# design.net
KiCad netlist of a schematic drawn in EasyEDA Pro
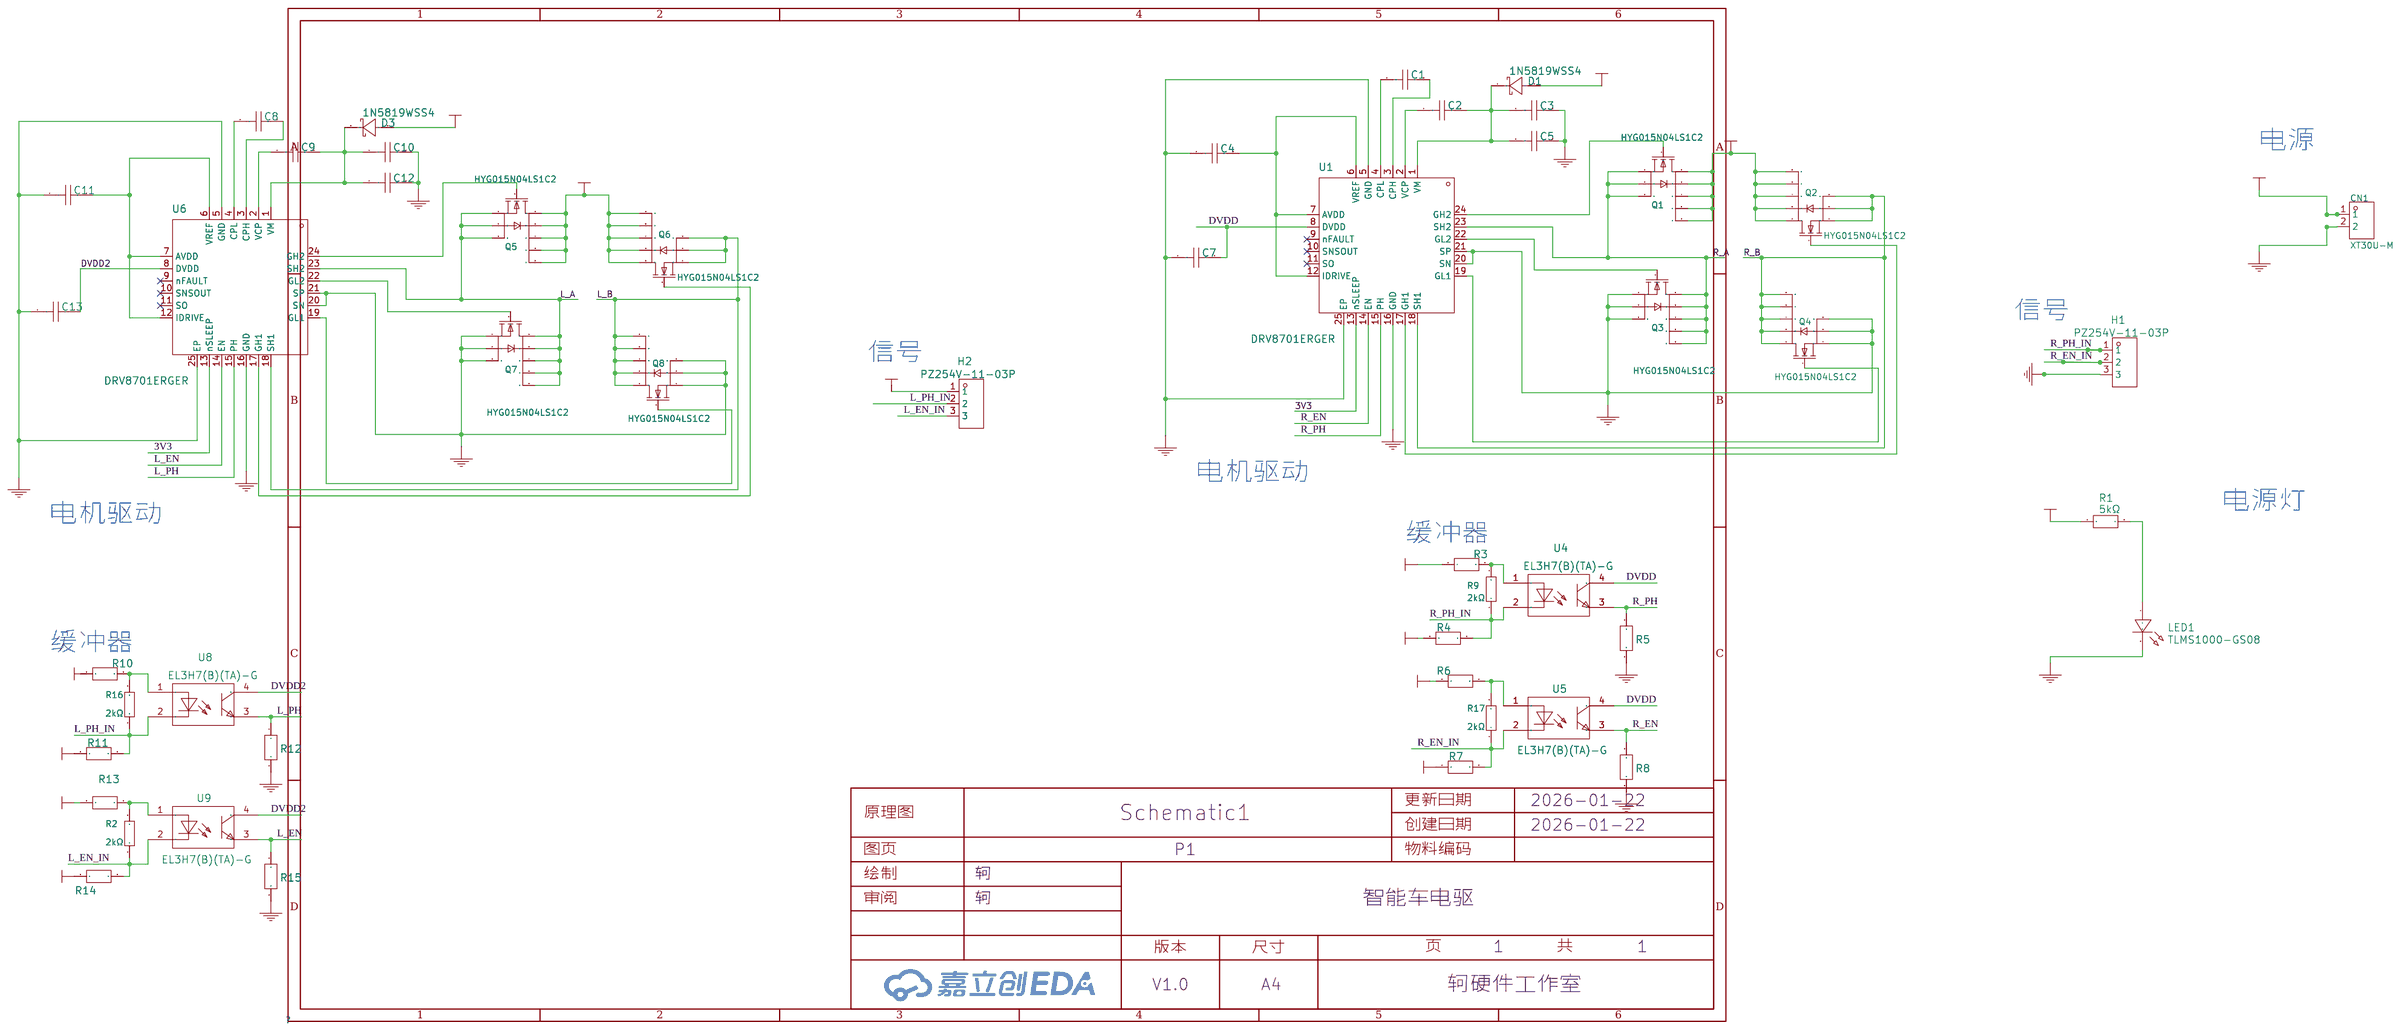
[diagram p0: schematic sheet]

(export (version "E")
  (design (tool "Eeschema 10.0.6"))
  (components
    (comp (ref "C1")
      (value "100nF")
      (fields (field (name "Manufacturer Part") "CC0805KRX7R9BB104"))
      (libsource (lib "easyedapro") (part "100nF"))
    )
    (comp (ref "C2")
      (value "1uF")
      (fields (field (name "Manufacturer Part") "CC0805KKX7R9BB105"))
      (libsource (lib "easyedapro") (part "1uF"))
    )
    (comp (ref "C3")
      (value "10nF")
      (fields (field (name "Manufacturer Part") "CC0805KRX7R9BB103"))
      (libsource (lib "easyedapro") (part "10uF"))
    )
    (comp (ref "C4")
      (value "1uF")
      (fields (field (name "Manufacturer Part") "CC0805KKX7R9BB105"))
      (libsource (lib "easyedapro") (part "1uF"))
    )
    (comp (ref "C5")
      (value "100nF")
      (fields (field (name "Manufacturer Part") "CC0805KRX7R9BB104"))
      (libsource (lib "easyedapro") (part "100nF"))
    )
    (comp (ref "C7")
      (value "1uF")
      (fields (field (name "Manufacturer Part") "CC0805KKX7R9BB105"))
      (libsource (lib "easyedapro") (part "1uF"))
    )
    (comp (ref "C8")
      (value "100nF")
      (fields (field (name "Manufacturer Part") "CC0805KRX7R9BB104"))
      (libsource (lib "easyedapro") (part "100nF"))
    )
    (comp (ref "C9")
      (value "1uF")
      (fields (field (name "Manufacturer Part") "CC0805KKX7R9BB105"))
      (libsource (lib "easyedapro") (part "1uF"))
    )
    (comp (ref "C10")
      (value "10nF")
      (fields (field (name "Manufacturer Part") "CC0805KRX7R9BB103"))
      (libsource (lib "easyedapro") (part "10uF"))
    )
    (comp (ref "C11")
      (value "1uF")
      (fields (field (name "Manufacturer Part") "CC0805KKX7R9BB105"))
      (libsource (lib "easyedapro") (part "1uF"))
    )
    (comp (ref "C12")
      (value "100nF")
      (fields (field (name "Manufacturer Part") "CC0805KRX7R9BB104"))
      (libsource (lib "easyedapro") (part "100nF"))
    )
    (comp (ref "C13")
      (value "1uF")
      (fields (field (name "Manufacturer Part") "CC0805KKX7R9BB105"))
      (libsource (lib "easyedapro") (part "1uF"))
    )
    (comp (ref "CN1")
      (value "XT30U-M")
      (fields (field (name "Manufacturer") "AMASS(艾迈斯)"))
      (libsource (lib "easyedapro") (part "XT30U-M"))
    )
    (comp (ref "D1")
      (value "1N5819WSS4")
      (fields (field (name "Manufacturer") "JSMSEMI(杰盛微)"))
      (libsource (lib "easyedapro") (part "1N5819WS S4"))
    )
    (comp (ref "D3")
      (value "1N5819WSS4")
      (fields (field (name "Manufacturer") "JSMSEMI(杰盛微)"))
      (libsource (lib "easyedapro") (part "1N5819WS S4"))
    )
    (comp (ref "H1")
      (value "PZ254V-11-03P")
      (fields (field (name "Manufacturer") "XFCN(兴飞)"))
      (libsource (lib "easyedapro") (part "PZ254V-11-03P_C2937625"))
    )
    (comp (ref "H2")
      (value "PZ254V-11-03P")
      (fields (field (name "Manufacturer") "XFCN(兴飞)"))
      (libsource (lib "easyedapro") (part "PZ254V-11-03P_C2937625"))
    )
    (comp (ref "LED1")
      (value "TLMS1000-GS08")
      (fields (field (name "Manufacturer") "VISHAY(威世)"))
      (libsource (lib "easyedapro") (part "LED-0603_G"))
    )
    (comp (ref "Q1")
      (value "HYG015N04LS1C2")
      (footprint "easyedapro:DFN-8_L5.9-W5.2-P1.27-LS6.2-BL")
      (fields (field (name "Manufacturer") "HUAYI(华羿微)"))
      (libsource (lib "easyedapro") (part "HYG015N04LS1C2"))
    )
    (comp (ref "Q2")
      (value "HYG015N04LS1C2")
      (footprint "easyedapro:DFN-8_L5.9-W5.2-P1.27-LS6.2-BL")
      (fields (field (name "Manufacturer") "HUAYI(华羿微)"))
      (libsource (lib "easyedapro") (part "HYG015N04LS1C2"))
    )
    (comp (ref "Q3")
      (value "HYG015N04LS1C2")
      (footprint "easyedapro:DFN-8_L5.9-W5.2-P1.27-LS6.2-BL")
      (fields (field (name "Manufacturer") "HUAYI(华羿微)"))
      (libsource (lib "easyedapro") (part "HYG015N04LS1C2"))
    )
    (comp (ref "Q4")
      (value "HYG015N04LS1C2")
      (footprint "easyedapro:DFN-8_L5.9-W5.2-P1.27-LS6.2-BL")
      (fields (field (name "Manufacturer") "HUAYI(华羿微)"))
      (libsource (lib "easyedapro") (part "HYG015N04LS1C2"))
    )
    (comp (ref "Q5")
      (value "HYG015N04LS1C2")
      (footprint "easyedapro:DFN-8_L5.9-W5.2-P1.27-LS6.2-BL")
      (fields (field (name "Manufacturer") "HUAYI(华羿微)"))
      (libsource (lib "easyedapro") (part "HYG015N04LS1C2"))
    )
    (comp (ref "Q6")
      (value "HYG015N04LS1C2")
      (footprint "easyedapro:DFN-8_L5.9-W5.2-P1.27-LS6.2-BL")
      (fields (field (name "Manufacturer") "HUAYI(华羿微)"))
      (libsource (lib "easyedapro") (part "HYG015N04LS1C2"))
    )
    (comp (ref "Q7")
      (value "HYG015N04LS1C2")
      (footprint "easyedapro:DFN-8_L5.9-W5.2-P1.27-LS6.2-BL")
      (fields (field (name "Manufacturer") "HUAYI(华羿微)"))
      (libsource (lib "easyedapro") (part "HYG015N04LS1C2"))
    )
    (comp (ref "Q8")
      (value "HYG015N04LS1C2")
      (footprint "easyedapro:DFN-8_L5.9-W5.2-P1.27-LS6.2-BL")
      (fields (field (name "Manufacturer") "HUAYI(华羿微)"))
      (libsource (lib "easyedapro") (part "HYG015N04LS1C2"))
    )
    (comp (ref "R1")
      (value "5kΩ")
      (fields (field (name "Manufacturer Part") "RC0603FR-072K2L"))
      (libsource (lib "easyedapro") (part "2.2KΩ"))
    )
    (comp (ref "R2")
      (value "2kΩ")
      (footprint "easyedapro:R0603")
      (description "电阻类型:厚膜电阻;阻值:2kΩ;精度:±1%;功率:100mW;")
      (fields
        (field (name "Manufacturer Part") "0603WAF2001T5E")
        (field (name "Manufacturer") "UNI-ROYAL(厚声)")
      )
      (libsource (lib "easyedapro") (part "0603WAF2001T5E"))
    )
    (comp (ref "R3")
      (value "1kΩ")
      (fields (field (name "Manufacturer Part") "RC0603FR-071KL"))
      (libsource (lib "easyedapro") (part "1k"))
    )
    (comp (ref "R4")
      (value "10kΩ")
      (fields (field (name "Manufacturer Part") "RC0603FR-0710KL"))
      (libsource (lib "easyedapro") (part "10K"))
    )
    (comp (ref "R5")
      (value "10kΩ")
      (fields (field (name "Manufacturer Part") "RC0603FR-0710KL"))
      (libsource (lib "easyedapro") (part "10K"))
    )
    (comp (ref "R6")
      (value "1kΩ")
      (fields (field (name "Manufacturer Part") "RC0603FR-071KL"))
      (libsource (lib "easyedapro") (part "1k"))
    )
    (comp (ref "R7")
      (value "10kΩ")
      (fields (field (name "Manufacturer Part") "RC0603FR-0710KL"))
      (libsource (lib "easyedapro") (part "10K"))
    )
    (comp (ref "R8")
      (value "10kΩ")
      (fields (field (name "Manufacturer Part") "RC0603FR-0710KL"))
      (libsource (lib "easyedapro") (part "10K"))
    )
    (comp (ref "R9")
      (value "2kΩ")
      (footprint "easyedapro:R0603")
      (description "电阻类型:厚膜电阻;阻值:2kΩ;精度:±1%;功率:100mW;")
      (fields
        (field (name "Manufacturer Part") "0603WAF2001T5E")
        (field (name "Manufacturer") "UNI-ROYAL(厚声)")
      )
      (libsource (lib "easyedapro") (part "0603WAF2001T5E"))
    )
    (comp (ref "R10")
      (value "1kΩ")
      (fields (field (name "Manufacturer Part") "RC0603FR-071KL"))
      (libsource (lib "easyedapro") (part "1k"))
    )
    (comp (ref "R11")
      (value "10kΩ")
      (fields (field (name "Manufacturer Part") "RC0603FR-0710KL"))
      (libsource (lib "easyedapro") (part "10K"))
    )
    (comp (ref "R12")
      (value "10kΩ")
      (fields (field (name "Manufacturer Part") "RC0603FR-0710KL"))
      (libsource (lib "easyedapro") (part "10K"))
    )
    (comp (ref "R13")
      (value "1kΩ")
      (fields (field (name "Manufacturer Part") "RC0603FR-071KL"))
      (libsource (lib "easyedapro") (part "1k"))
    )
    (comp (ref "R14")
      (value "10kΩ")
      (fields (field (name "Manufacturer Part") "RC0603FR-0710KL"))
      (libsource (lib "easyedapro") (part "10K"))
    )
    (comp (ref "R15")
      (value "10kΩ")
      (fields (field (name "Manufacturer Part") "RC0603FR-0710KL"))
      (libsource (lib "easyedapro") (part "10K"))
    )
    (comp (ref "R16")
      (value "2kΩ")
      (footprint "easyedapro:R0603")
      (description "电阻类型:厚膜电阻;阻值:2kΩ;精度:±1%;功率:100mW;")
      (fields
        (field (name "Manufacturer Part") "0603WAF2001T5E")
        (field (name "Manufacturer") "UNI-ROYAL(厚声)")
      )
      (libsource (lib "easyedapro") (part "0603WAF2001T5E"))
    )
    (comp (ref "R17")
      (value "2kΩ")
      (footprint "easyedapro:R0603")
      (description "电阻类型:厚膜电阻;阻值:2kΩ;精度:±1%;功率:100mW;")
      (fields
        (field (name "Manufacturer Part") "0603WAF2001T5E")
        (field (name "Manufacturer") "UNI-ROYAL(厚声)")
      )
      (libsource (lib "easyedapro") (part "0603WAF2001T5E"))
    )
    (comp (ref "U1")
      (value "DRV8701ERGER")
      (fields (field (name "Manufacturer") "TI(德州仪器)"))
      (libsource (lib "easyedapro") (part "DRV8701ERGET"))
    )
    (comp (ref "U4")
      (value "EL3H7(B)(TA)-G")
      (fields (field (name "Manufacturer") "EVERLIGHT(亿光)"))
      (libsource (lib "easyedapro") (part "EL3H7(B)(TA)-G"))
    )
    (comp (ref "U5")
      (value "EL3H7(B)(TA)-G")
      (fields (field (name "Manufacturer") "EVERLIGHT(亿光)"))
      (libsource (lib "easyedapro") (part "EL3H7(B)(TA)-G"))
    )
    (comp (ref "U6")
      (value "DRV8701ERGER")
      (fields (field (name "Manufacturer") "TI(德州仪器)"))
      (libsource (lib "easyedapro") (part "DRV8701ERGET"))
    )
    (comp (ref "U8")
      (value "EL3H7(B)(TA)-G")
      (fields (field (name "Manufacturer") "EVERLIGHT(亿光)"))
      (libsource (lib "easyedapro") (part "EL3H7(B)(TA)-G"))
    )
    (comp (ref "U9")
      (value "EL3H7(B)(TA)-G")
      (fields (field (name "Manufacturer") "EVERLIGHT(亿光)"))
      (libsource (lib "easyedapro") (part "EL3H7(B)(TA)-G"))
    )
  )
  (nets
    (net (code "1") (name "/DVDD") (class "Default")
      (node (ref "C7") (pin "2") (pinfunction "2_2") (pintype "input"))
      (node (ref "U1") (pin "8") (pinfunction "DVDD_8") (pintype "input"))
      (node (ref "U4") (pin "4") (pinfunction "COL_4") (pintype "input"))
      (node (ref "U5") (pin "4") (pinfunction "COL_4") (pintype "input"))
    )
    (net (code "2") (name "/DVDD2") (class "Default")
      (node (ref "C13") (pin "2") (pinfunction "2_2") (pintype "input"))
      (node (ref "U6") (pin "8") (pinfunction "DVDD_8") (pintype "input"))
      (node (ref "U8") (pin "4") (pinfunction "COL_4") (pintype "input"))
      (node (ref "U9") (pin "4") (pinfunction "COL_4") (pintype "input"))
    )
    (net (code "3") (name "/L_A") (class "Default")
      (node (ref "Q5") (pin "1") (pinfunction "S_1") (pintype "input"))
      (node (ref "Q5") (pin "2") (pinfunction "S_2") (pintype "input"))
      (node (ref "Q5") (pin "3") (pinfunction "S_3") (pintype "input"))
      (node (ref "Q7") (pin "5") (pinfunction "D_5") (pintype "input"))
      (node (ref "Q7") (pin "6") (pinfunction "D_6") (pintype "input"))
      (node (ref "Q7") (pin "7") (pinfunction "D_7") (pintype "input"))
      (node (ref "Q7") (pin "8") (pinfunction "D_8") (pintype "input"))
      (node (ref "Q7") (pin "9") (pinfunction "D_9") (pintype "input"))
      (node (ref "U6") (pin "23") (pinfunction "SH2_23") (pintype "input"))
    )
    (net (code "4") (name "/L_B") (class "Default")
      (node (ref "Q6") (pin "1") (pinfunction "S_1") (pintype "input"))
      (node (ref "Q6") (pin "2") (pinfunction "S_2") (pintype "input"))
      (node (ref "Q6") (pin "3") (pinfunction "S_3") (pintype "input"))
      (node (ref "Q8") (pin "5") (pinfunction "D_5") (pintype "input"))
      (node (ref "Q8") (pin "6") (pinfunction "D_6") (pintype "input"))
      (node (ref "Q8") (pin "7") (pinfunction "D_7") (pintype "input"))
      (node (ref "Q8") (pin "8") (pinfunction "D_8") (pintype "input"))
      (node (ref "Q8") (pin "9") (pinfunction "D_9") (pintype "input"))
      (node (ref "U6") (pin "18") (pinfunction "SH1_18") (pintype "input"))
    )
    (net (code "5") (name "/L_EN") (class "Default")
      (node (ref "R15") (pin "1") (pinfunction "1_1") (pintype "input"))
      (node (ref "U6") (pin "14") (pinfunction "EN_14") (pintype "input"))
      (node (ref "U9") (pin "3") (pinfunction "EM_3") (pintype "input"))
    )
    (net (code "6") (name "/L_EN_IN") (class "Default")
      (node (ref "H2") (pin "3") (pinfunction "3_3") (pintype "input"))
      (node (ref "R14") (pin "2") (pinfunction "2_2") (pintype "input"))
      (node (ref "R2") (pin "1") (pinfunction "1_1") (pintype "input"))
      (node (ref "U9") (pin "2") (pinfunction "CAT_2") (pintype "input"))
    )
    (net (code "7") (name "/L_PH") (class "Default")
      (node (ref "R12") (pin "1") (pinfunction "1_1") (pintype "input"))
      (node (ref "U6") (pin "15") (pinfunction "PH_15") (pintype "input"))
      (node (ref "U8") (pin "3") (pinfunction "EM_3") (pintype "input"))
    )
    (net (code "8") (name "/L_PH_IN") (class "Default")
      (node (ref "H2") (pin "2") (pinfunction "2_2") (pintype "input"))
      (node (ref "R11") (pin "1") (pinfunction "1_1") (pintype "input"))
      (node (ref "R16") (pin "1") (pinfunction "1_1") (pintype "input"))
      (node (ref "U8") (pin "2") (pinfunction "CAT_2") (pintype "input"))
    )
    (net (code "9") (name "/R_A") (class "Default")
      (node (ref "Q1") (pin "1") (pinfunction "S_1") (pintype "input"))
      (node (ref "Q1") (pin "2") (pinfunction "S_2") (pintype "input"))
      (node (ref "Q1") (pin "3") (pinfunction "S_3") (pintype "input"))
      (node (ref "Q3") (pin "5") (pinfunction "D_5") (pintype "input"))
      (node (ref "Q3") (pin "6") (pinfunction "D_6") (pintype "input"))
      (node (ref "Q3") (pin "7") (pinfunction "D_7") (pintype "input"))
      (node (ref "Q3") (pin "8") (pinfunction "D_8") (pintype "input"))
      (node (ref "Q3") (pin "9") (pinfunction "D_9") (pintype "input"))
      (node (ref "U1") (pin "23") (pinfunction "SH2_23") (pintype "input"))
    )
    (net (code "10") (name "/R_B") (class "Default")
      (node (ref "Q2") (pin "1") (pinfunction "S_1") (pintype "input"))
      (node (ref "Q2") (pin "2") (pinfunction "S_2") (pintype "input"))
      (node (ref "Q2") (pin "3") (pinfunction "S_3") (pintype "input"))
      (node (ref "Q4") (pin "5") (pinfunction "D_5") (pintype "input"))
      (node (ref "Q4") (pin "6") (pinfunction "D_6") (pintype "input"))
      (node (ref "Q4") (pin "7") (pinfunction "D_7") (pintype "input"))
      (node (ref "Q4") (pin "8") (pinfunction "D_8") (pintype "input"))
      (node (ref "Q4") (pin "9") (pinfunction "D_9") (pintype "input"))
      (node (ref "U1") (pin "18") (pinfunction "SH1_18") (pintype "input"))
    )
    (net (code "11") (name "/R_EN") (class "Default")
      (node (ref "R8") (pin "1") (pinfunction "1_1") (pintype "input"))
      (node (ref "U1") (pin "14") (pinfunction "EN_14") (pintype "input"))
      (node (ref "U5") (pin "3") (pinfunction "EM_3") (pintype "input"))
    )
    (net (code "12") (name "/R_EN_IN") (class "Default")
      (node (ref "H1") (pin "2") (pinfunction "2_2") (pintype "input"))
      (node (ref "R17") (pin "1") (pinfunction "1_1") (pintype "input"))
      (node (ref "R7") (pin "2") (pinfunction "2_2") (pintype "input"))
      (node (ref "U5") (pin "2") (pinfunction "CAT_2") (pintype "input"))
    )
    (net (code "13") (name "/R_PH") (class "Default")
      (node (ref "R5") (pin "1") (pinfunction "1_1") (pintype "input"))
      (node (ref "U1") (pin "15") (pinfunction "PH_15") (pintype "input"))
      (node (ref "U4") (pin "3") (pinfunction "EM_3") (pintype "input"))
    )
    (net (code "14") (name "/R_PH_IN") (class "Default")
      (node (ref "H1") (pin "1") (pinfunction "1_1") (pintype "input"))
      (node (ref "R4") (pin "1") (pinfunction "1_1") (pintype "input"))
      (node (ref "R9") (pin "1") (pinfunction "1_1") (pintype "input"))
      (node (ref "U4") (pin "2") (pinfunction "CAT_2") (pintype "input"))
    )
    (net (code "15") (name "3V3") (class "Default")
      (node (ref "H2") (pin "1") (pinfunction "1_1") (pintype "input"))
      (node (ref "R10") (pin "1") (pinfunction "1_1") (pintype "input"))
      (node (ref "R11") (pin "2") (pinfunction "2_2") (pintype "input"))
      (node (ref "R13") (pin "2") (pinfunction "2_2") (pintype "input"))
      (node (ref "R14") (pin "1") (pinfunction "1_1") (pintype "input"))
      (node (ref "R3") (pin "1") (pinfunction "1_1") (pintype "input"))
      (node (ref "R4") (pin "2") (pinfunction "2_2") (pintype "input"))
      (node (ref "R6") (pin "2") (pinfunction "2_2") (pintype "input"))
      (node (ref "R7") (pin "1") (pinfunction "1_1") (pintype "input"))
      (node (ref "U1") (pin "13") (pinfunction "nSLEEP_13") (pintype "input"))
      (node (ref "U6") (pin "13") (pinfunction "nSLEEP_13") (pintype "input"))
    )
    (net (code "16") (name "GND") (class "Default")
      (node (ref "C10") (pin "2") (pinfunction "2_2") (pintype "input"))
      (node (ref "C11") (pin "1") (pinfunction "1_1") (pintype "input"))
      (node (ref "C12") (pin "2") (pinfunction "2_2") (pintype "input"))
      (node (ref "C13") (pin "1") (pinfunction "1_1") (pintype "input"))
      (node (ref "C3") (pin "2") (pinfunction "2_2") (pintype "input"))
      (node (ref "C4") (pin "1") (pinfunction "1_1") (pintype "input"))
      (node (ref "C5") (pin "2") (pinfunction "2_2") (pintype "input"))
      (node (ref "C7") (pin "1") (pinfunction "1_1") (pintype "input"))
      (node (ref "CN1") (pin "2") (pinfunction "2_2") (pintype "input"))
      (node (ref "H1") (pin "3") (pinfunction "3_3") (pintype "input"))
      (node (ref "LED1") (pin "2") (pinfunction "2_2") (pintype "input"))
      (node (ref "Q3") (pin "1") (pinfunction "S_1") (pintype "input"))
      (node (ref "Q3") (pin "2") (pinfunction "S_2") (pintype "input"))
      (node (ref "Q3") (pin "3") (pinfunction "S_3") (pintype "input"))
      (node (ref "Q4") (pin "1") (pinfunction "S_1") (pintype "input"))
      (node (ref "Q4") (pin "2") (pinfunction "S_2") (pintype "input"))
      (node (ref "Q4") (pin "3") (pinfunction "S_3") (pintype "input"))
      (node (ref "Q7") (pin "1") (pinfunction "S_1") (pintype "input"))
      (node (ref "Q7") (pin "2") (pinfunction "S_2") (pintype "input"))
      (node (ref "Q7") (pin "3") (pinfunction "S_3") (pintype "input"))
      (node (ref "Q8") (pin "1") (pinfunction "S_1") (pintype "input"))
      (node (ref "Q8") (pin "2") (pinfunction "S_2") (pintype "input"))
      (node (ref "Q8") (pin "3") (pinfunction "S_3") (pintype "input"))
      (node (ref "R12") (pin "2") (pinfunction "2_2") (pintype "input"))
      (node (ref "R15") (pin "2") (pinfunction "2_2") (pintype "input"))
      (node (ref "R5") (pin "2") (pinfunction "2_2") (pintype "input"))
      (node (ref "R8") (pin "2") (pinfunction "2_2") (pintype "input"))
      (node (ref "U1") (pin "16") (pinfunction "GND_16") (pintype "input"))
      (node (ref "U1") (pin "20") (pinfunction "SN_20") (pintype "input"))
      (node (ref "U1") (pin "21") (pinfunction "SP_21") (pintype "input"))
      (node (ref "U1") (pin "25") (pinfunction "EP_25") (pintype "input"))
      (node (ref "U1") (pin "5") (pinfunction "GND_5") (pintype "input"))
      (node (ref "U6") (pin "16") (pinfunction "GND_16") (pintype "input"))
      (node (ref "U6") (pin "20") (pinfunction "SN_20") (pintype "input"))
      (node (ref "U6") (pin "21") (pinfunction "SP_21") (pintype "input"))
      (node (ref "U6") (pin "25") (pinfunction "EP_25") (pintype "input"))
      (node (ref "U6") (pin "5") (pinfunction "GND_5") (pintype "input"))
    )
    (net (code "17") (name "Net-(D1-C)") (class "Default")
      (node (ref "C2") (pin "2") (pinfunction "2_2") (pintype "input"))
      (node (ref "C3") (pin "1") (pinfunction "1_1") (pintype "input"))
      (node (ref "C5") (pin "1") (pinfunction "1_1") (pintype "input"))
      (node (ref "D1") (pin "1") (pinfunction "C_1") (pintype "input"))
      (node (ref "U1") (pin "1") (pinfunction "VM_1") (pintype "input"))
    )
    (net (code "18") (name "Net-(D3-C)") (class "Default")
      (node (ref "C10") (pin "1") (pinfunction "1_1") (pintype "input"))
      (node (ref "C12") (pin "1") (pinfunction "1_1") (pintype "input"))
      (node (ref "C9") (pin "2") (pinfunction "2_2") (pintype "input"))
      (node (ref "D3") (pin "1") (pinfunction "C_1") (pintype "input"))
      (node (ref "U6") (pin "1") (pinfunction "VM_1") (pintype "input"))
    )
    (net (code "19") (name "Net-(LED1-Pad1)") (class "Default")
      (node (ref "LED1") (pin "1") (pinfunction "1_1") (pintype "input"))
      (node (ref "R1") (pin "2") (pinfunction "2_2") (pintype "input"))
    )
    (net (code "20") (name "Net-(Q1-G)") (class "Default")
      (node (ref "Q1") (pin "4") (pinfunction "G_4") (pintype "input"))
      (node (ref "U1") (pin "24") (pinfunction "GH2_24") (pintype "input"))
    )
    (net (code "21") (name "Net-(Q2-G)") (class "Default")
      (node (ref "Q2") (pin "4") (pinfunction "G_4") (pintype "input"))
      (node (ref "U1") (pin "17") (pinfunction "GH1_17") (pintype "input"))
    )
    (net (code "22") (name "Net-(Q3-G)") (class "Default")
      (node (ref "Q3") (pin "4") (pinfunction "G_4") (pintype "input"))
      (node (ref "U1") (pin "22") (pinfunction "GL2_22") (pintype "input"))
    )
    (net (code "23") (name "Net-(Q4-G)") (class "Default")
      (node (ref "Q4") (pin "4") (pinfunction "G_4") (pintype "input"))
      (node (ref "U1") (pin "19") (pinfunction "GL1_19") (pintype "input"))
    )
    (net (code "24") (name "Net-(Q5-G)") (class "Default")
      (node (ref "Q5") (pin "4") (pinfunction "G_4") (pintype "input"))
      (node (ref "U6") (pin "24") (pinfunction "GH2_24") (pintype "input"))
    )
    (net (code "25") (name "Net-(Q6-G)") (class "Default")
      (node (ref "Q6") (pin "4") (pinfunction "G_4") (pintype "input"))
      (node (ref "U6") (pin "17") (pinfunction "GH1_17") (pintype "input"))
    )
    (net (code "26") (name "Net-(Q7-G)") (class "Default")
      (node (ref "Q7") (pin "4") (pinfunction "G_4") (pintype "input"))
      (node (ref "U6") (pin "22") (pinfunction "GL2_22") (pintype "input"))
    )
    (net (code "27") (name "Net-(Q8-G)") (class "Default")
      (node (ref "Q8") (pin "4") (pinfunction "G_4") (pintype "input"))
      (node (ref "U6") (pin "19") (pinfunction "GL1_19") (pintype "input"))
    )
    (net (code "28") (name "Net-(U1-AVDD)") (class "Default")
      (node (ref "C4") (pin "2") (pinfunction "2_2") (pintype "input"))
      (node (ref "U1") (pin "12") (pinfunction "IDRIVE_12") (pintype "input"))
      (node (ref "U1") (pin "6") (pinfunction "VREF_6") (pintype "input"))
      (node (ref "U1") (pin "7") (pinfunction "AVDD_7") (pintype "input"))
    )
    (net (code "29") (name "Net-(U1-CPH)") (class "Default")
      (node (ref "C1") (pin "2") (pinfunction "2_2") (pintype "input"))
      (node (ref "U1") (pin "3") (pinfunction "CPH_3") (pintype "input"))
    )
    (net (code "30") (name "Net-(U1-CPL)") (class "Default")
      (node (ref "C1") (pin "1") (pinfunction "1_1") (pintype "input"))
      (node (ref "U1") (pin "4") (pinfunction "CPL_4") (pintype "input"))
    )
    (net (code "31") (name "Net-(U1-VCP)") (class "Default")
      (node (ref "C2") (pin "1") (pinfunction "1_1") (pintype "input"))
      (node (ref "U1") (pin "2") (pinfunction "VCP_2") (pintype "input"))
    )
    (net (code "32") (name "Net-(U4-AN)") (class "Default")
      (node (ref "R3") (pin "2") (pinfunction "2_2") (pintype "input"))
      (node (ref "R9") (pin "2") (pinfunction "2_2") (pintype "input"))
      (node (ref "U4") (pin "1") (pinfunction "AN_1") (pintype "input"))
    )
    (net (code "33") (name "Net-(U5-AN)") (class "Default")
      (node (ref "R17") (pin "2") (pinfunction "2_2") (pintype "input"))
      (node (ref "R6") (pin "1") (pinfunction "1_1") (pintype "input"))
      (node (ref "U5") (pin "1") (pinfunction "AN_1") (pintype "input"))
    )
    (net (code "34") (name "Net-(U6-AVDD)") (class "Default")
      (node (ref "C11") (pin "2") (pinfunction "2_2") (pintype "input"))
      (node (ref "U6") (pin "12") (pinfunction "IDRIVE_12") (pintype "input"))
      (node (ref "U6") (pin "6") (pinfunction "VREF_6") (pintype "input"))
      (node (ref "U6") (pin "7") (pinfunction "AVDD_7") (pintype "input"))
    )
    (net (code "35") (name "Net-(U6-CPH)") (class "Default")
      (node (ref "C8") (pin "2") (pinfunction "2_2") (pintype "input"))
      (node (ref "U6") (pin "3") (pinfunction "CPH_3") (pintype "input"))
    )
    (net (code "36") (name "Net-(U6-CPL)") (class "Default")
      (node (ref "C8") (pin "1") (pinfunction "1_1") (pintype "input"))
      (node (ref "U6") (pin "4") (pinfunction "CPL_4") (pintype "input"))
    )
    (net (code "37") (name "Net-(U6-VCP)") (class "Default")
      (node (ref "C9") (pin "1") (pinfunction "1_1") (pintype "input"))
      (node (ref "U6") (pin "2") (pinfunction "VCP_2") (pintype "input"))
    )
    (net (code "38") (name "Net-(U8-AN)") (class "Default")
      (node (ref "R10") (pin "2") (pinfunction "2_2") (pintype "input"))
      (node (ref "R16") (pin "2") (pinfunction "2_2") (pintype "input"))
      (node (ref "U8") (pin "1") (pinfunction "AN_1") (pintype "input"))
    )
    (net (code "39") (name "Net-(U9-AN)") (class "Default")
      (node (ref "R13") (pin "1") (pinfunction "1_1") (pintype "input"))
      (node (ref "R2") (pin "2") (pinfunction "2_2") (pintype "input"))
      (node (ref "U9") (pin "1") (pinfunction "AN_1") (pintype "input"))
    )
    (net (code "40") (name "VM") (class "Default")
      (node (ref "CN1") (pin "1") (pinfunction "1_1") (pintype "input"))
      (node (ref "D1") (pin "2") (pinfunction "A_2") (pintype "input"))
      (node (ref "D3") (pin "2") (pinfunction "A_2") (pintype "input"))
      (node (ref "Q1") (pin "5") (pinfunction "D_5") (pintype "input"))
      (node (ref "Q1") (pin "6") (pinfunction "D_6") (pintype "input"))
      (node (ref "Q1") (pin "7") (pinfunction "D_7") (pintype "input"))
      (node (ref "Q1") (pin "8") (pinfunction "D_8") (pintype "input"))
      (node (ref "Q1") (pin "9") (pinfunction "D_9") (pintype "input"))
      (node (ref "Q2") (pin "5") (pinfunction "D_5") (pintype "input"))
      (node (ref "Q2") (pin "6") (pinfunction "D_6") (pintype "input"))
      (node (ref "Q2") (pin "7") (pinfunction "D_7") (pintype "input"))
      (node (ref "Q2") (pin "8") (pinfunction "D_8") (pintype "input"))
      (node (ref "Q2") (pin "9") (pinfunction "D_9") (pintype "input"))
      (node (ref "Q5") (pin "5") (pinfunction "D_5") (pintype "input"))
      (node (ref "Q5") (pin "6") (pinfunction "D_6") (pintype "input"))
      (node (ref "Q5") (pin "7") (pinfunction "D_7") (pintype "input"))
      (node (ref "Q5") (pin "8") (pinfunction "D_8") (pintype "input"))
      (node (ref "Q5") (pin "9") (pinfunction "D_9") (pintype "input"))
      (node (ref "Q6") (pin "5") (pinfunction "D_5") (pintype "input"))
      (node (ref "Q6") (pin "6") (pinfunction "D_6") (pintype "input"))
      (node (ref "Q6") (pin "7") (pinfunction "D_7") (pintype "input"))
      (node (ref "Q6") (pin "8") (pinfunction "D_8") (pintype "input"))
      (node (ref "Q6") (pin "9") (pinfunction "D_9") (pintype "input"))
      (node (ref "R1") (pin "1") (pinfunction "1_1") (pintype "input"))
    )
    (net (code "41") (name "unconnected-(U1-SNSOUT-Pad10)") (class "Default")
      (node (ref "U1") (pin "10") (pinfunction "SNSOUT_10") (pintype "input+no_connect"))
    )
    (net (code "42") (name "unconnected-(U1-SO-Pad11)") (class "Default")
      (node (ref "U1") (pin "11") (pinfunction "SO_11") (pintype "input+no_connect"))
    )
    (net (code "43") (name "unconnected-(U1-nFAULT-Pad9)") (class "Default")
      (node (ref "U1") (pin "9") (pinfunction "nFAULT_9") (pintype "input+no_connect"))
    )
    (net (code "44") (name "unconnected-(U6-SNSOUT-Pad10)") (class "Default")
      (node (ref "U6") (pin "10") (pinfunction "SNSOUT_10") (pintype "input+no_connect"))
    )
    (net (code "45") (name "unconnected-(U6-SO-Pad11)") (class "Default")
      (node (ref "U6") (pin "11") (pinfunction "SO_11") (pintype "input+no_connect"))
    )
    (net (code "46") (name "unconnected-(U6-nFAULT-Pad9)") (class "Default")
      (node (ref "U6") (pin "9") (pinfunction "nFAULT_9") (pintype "input+no_connect"))
    )
  )
)
